# Inputs.net
KiCad netlist of a schematic drawn in Altium Designer
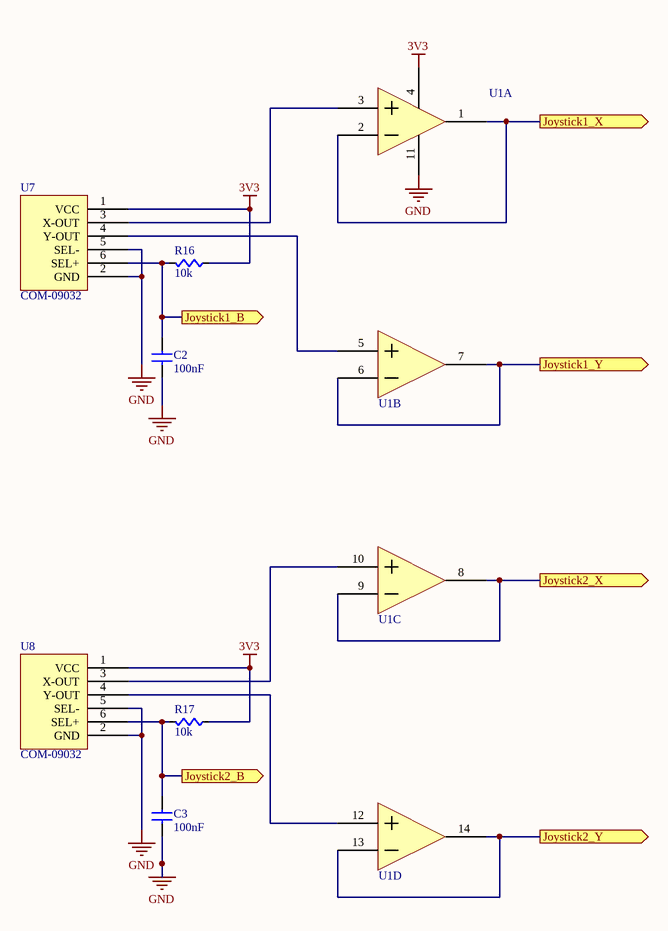
[diagram p0: Inputs.SchDoc]

(export (version "E")
  (design (tool "Eeschema 10.0.6"))
  (components
    (comp (ref "C2")
      (value "100nF")
      (footprint "CAPC0603")
      (fields (field (name "Comment") "Cap"))
      (libsource (lib "SubjuGator8") (part "Cap"))
    )
    (comp (ref "C3")
      (value "100nF")
      (footprint "CAPC0603")
      (fields (field (name "Comment") "Cap"))
      (libsource (lib "SubjuGator8") (part "Cap"))
    )
    (comp (ref "R16")
      (value "10k")
      (footprint "RES0603")
      (fields (field (name "Comment") "Res"))
      (libsource (lib "SubjuGator8") (part "Res"))
    )
    (comp (ref "R17")
      (value "10k")
      (footprint "RES0603")
      (fields (field (name "Comment") "Res"))
      (libsource (lib "SubjuGator8") (part "Res"))
    )
    (comp (ref "U1")
      (value "MCP6L04")
      (footprint "MCP6L04T-E/SL")
      (description "Quad Op Amp Rail-to-Rail 1Mhz")
      (libsource (lib "SubjuGator8") (part "MCP6L04"))
    )
    (comp (ref "U7")
      (value "COM-09032")
      (footprint "Joystick")
      (description "2 Axis 10 kOhms Through Hole Joystick Potentiometer")
      (libsource (lib "SubjuGator8") (part "COM-09032"))
    )
    (comp (ref "U8")
      (value "COM-09032")
      (footprint "Joystick")
      (description "2 Axis 10 kOhms Through Hole Joystick Potentiometer")
      (libsource (lib "SubjuGator8") (part "COM-09032"))
    )
  )
  (nets
    (net (code "1") (name "/Joystick1_B") (class "Default")
      (node (ref "C2") (pin "1") (pinfunction "A_1") (pintype "passive"))
      (node (ref "R16") (pin "1") (pinfunction "A_1") (pintype "passive"))
      (node (ref "U7") (pin "6") (pinfunction "SEL+_6") (pintype "passive"))
    )
    (net (code "2") (name "/Joystick1_X") (class "Default")
      (node (ref "U1") (pin "1") (pinfunction "VOUTA_1") (pintype "passive"))
      (node (ref "U1") (pin "2") (pinfunction "VINA-_2") (pintype "passive"))
    )
    (net (code "3") (name "/Joystick1_Y") (class "Default")
      (node (ref "U1") (pin "6") (pinfunction "VINB-_6") (pintype "passive"))
      (node (ref "U1") (pin "7") (pinfunction "VOUTB_7") (pintype "passive"))
    )
    (net (code "4") (name "/Joystick2_B") (class "Default")
      (node (ref "C3") (pin "1") (pinfunction "A_1") (pintype "passive"))
      (node (ref "R17") (pin "1") (pinfunction "A_1") (pintype "passive"))
      (node (ref "U8") (pin "6") (pinfunction "SEL+_6") (pintype "passive"))
    )
    (net (code "5") (name "/Joystick2_X") (class "Default")
      (node (ref "U1") (pin "8") (pinfunction "VOUTC_8") (pintype "passive"))
      (node (ref "U1") (pin "9") (pinfunction "VINC-_9") (pintype "passive"))
    )
    (net (code "6") (name "/Joystick2_Y") (class "Default")
      (node (ref "U1") (pin "13") (pinfunction "VIND-_13") (pintype "passive"))
      (node (ref "U1") (pin "14") (pinfunction "VOUTD_14") (pintype "passive"))
    )
    (net (code "7") (name "3V3") (class "Default")
      (node (ref "R16") (pin "2") (pinfunction "B_2") (pintype "passive"))
      (node (ref "R17") (pin "2") (pinfunction "B_2") (pintype "passive"))
      (node (ref "U1") (pin "4") (pinfunction "VDD_4") (pintype "passive"))
      (node (ref "U7") (pin "1") (pinfunction "VCC_1") (pintype "passive"))
      (node (ref "U8") (pin "1") (pinfunction "VCC_1") (pintype "passive"))
    )
    (net (code "8") (name "GND") (class "Default")
      (node (ref "C2") (pin "2") (pinfunction "B_2") (pintype "passive"))
      (node (ref "C3") (pin "2") (pinfunction "B_2") (pintype "passive"))
      (node (ref "U1") (pin "11") (pinfunction "VSS_11") (pintype "passive"))
      (node (ref "U7") (pin "2") (pinfunction "GND_2") (pintype "passive"))
      (node (ref "U7") (pin "5") (pinfunction "SEL-_5") (pintype "passive"))
      (node (ref "U8") (pin "2") (pinfunction "GND_2") (pintype "passive"))
      (node (ref "U8") (pin "5") (pinfunction "SEL-_5") (pintype "passive"))
    )
    (net (code "9") (name "Net-(U1A-VINA+)") (class "Default")
      (node (ref "U1") (pin "3") (pinfunction "VINA+_3") (pintype "passive"))
      (node (ref "U7") (pin "3") (pinfunction "X-OUT_3") (pintype "passive"))
    )
    (net (code "10") (name "Net-(U1B-VINB+)") (class "Default")
      (node (ref "U1") (pin "5") (pinfunction "VINB+_5") (pintype "passive"))
      (node (ref "U7") (pin "4") (pinfunction "Y-OUT_4") (pintype "passive"))
    )
    (net (code "11") (name "Net-(U1C-VINC+)") (class "Default")
      (node (ref "U1") (pin "10") (pinfunction "VINC+_10") (pintype "passive"))
      (node (ref "U8") (pin "3") (pinfunction "X-OUT_3") (pintype "passive"))
    )
    (net (code "12") (name "Net-(U1D-VIND+)") (class "Default")
      (node (ref "U1") (pin "12") (pinfunction "VIND+_12") (pintype "passive"))
      (node (ref "U8") (pin "4") (pinfunction "Y-OUT_4") (pintype "passive"))
    )
  )
)
